# TeensyRF.net
KiCad netlist of a schematic drawn in EAGLE
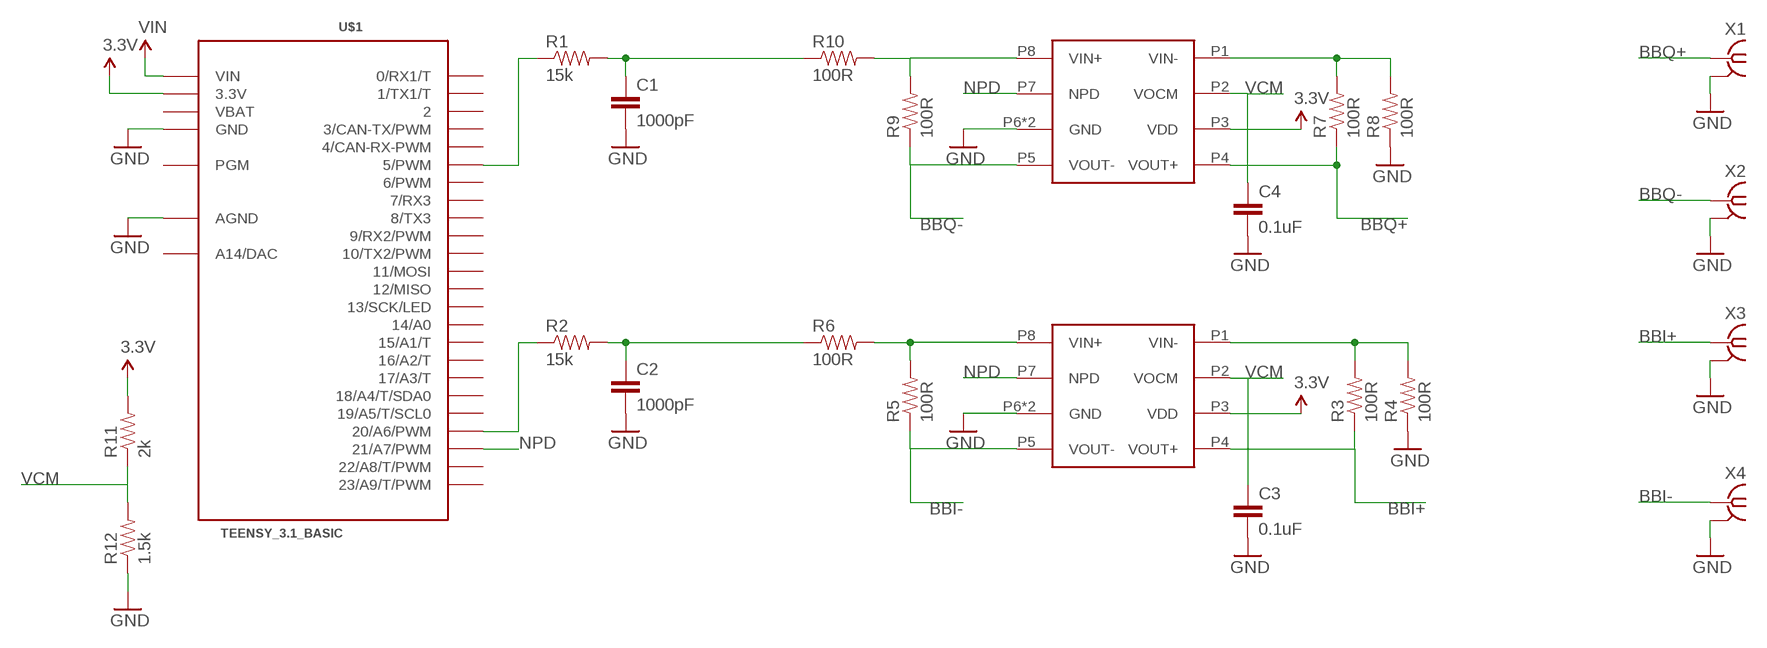
[diagram p0: schematic, sheet 1]

(export (version "E")
  (design (tool "Eeschema 10.0.6"))
  (components
    (comp (ref "C1")
      (value "1000pF")
      (footprint "eagle-import:0805")
      (libsource (lib "eagle-import") (part "CAP0805"))
    )
    (comp (ref "C2")
      (value "1000pF")
      (footprint "eagle-import:0805")
      (libsource (lib "eagle-import") (part "CAP0805"))
    )
    (comp (ref "C3")
      (value "0.1uF")
      (footprint "eagle-import:0805")
      (libsource (lib "eagle-import") (part "CAP0805"))
    )
    (comp (ref "C4")
      (value "0.1uF")
      (footprint "eagle-import:0805")
      (libsource (lib "eagle-import") (part "CAP0805"))
    )
    (comp (ref "R1")
      (value "15k")
      (footprint "eagle-import:0805")
      (libsource (lib "eagle-import") (part "RESISTOR0805-RES"))
    )
    (comp (ref "R2")
      (value "15k")
      (footprint "eagle-import:0805")
      (libsource (lib "eagle-import") (part "RESISTOR0805-RES"))
    )
    (comp (ref "R3")
      (value "100R")
      (footprint "eagle-import:0805")
      (libsource (lib "eagle-import") (part "RESISTOR0805-RES"))
    )
    (comp (ref "R4")
      (value "100R")
      (footprint "eagle-import:0805")
      (libsource (lib "eagle-import") (part "RESISTOR0805-RES"))
    )
    (comp (ref "R5")
      (value "100R")
      (footprint "eagle-import:0805")
      (libsource (lib "eagle-import") (part "RESISTOR0805-RES"))
    )
    (comp (ref "R6")
      (value "100R")
      (footprint "eagle-import:0805")
      (libsource (lib "eagle-import") (part "RESISTOR0805-RES"))
    )
    (comp (ref "R7")
      (value "100R")
      (footprint "eagle-import:0805")
      (libsource (lib "eagle-import") (part "RESISTOR0805-RES"))
    )
    (comp (ref "R8")
      (value "100R")
      (footprint "eagle-import:0805")
      (libsource (lib "eagle-import") (part "RESISTOR0805-RES"))
    )
    (comp (ref "R9")
      (value "100R")
      (footprint "eagle-import:0805")
      (libsource (lib "eagle-import") (part "RESISTOR0805-RES"))
    )
    (comp (ref "R10")
      (value "100R")
      (footprint "eagle-import:0805")
      (libsource (lib "eagle-import") (part "RESISTOR0805-RES"))
    )
    (comp (ref "R11")
      (value "2k")
      (footprint "eagle-import:0805")
      (libsource (lib "eagle-import") (part "RESISTOR0805-RES"))
    )
    (comp (ref "R12")
      (value "1.5k")
      (footprint "eagle-import:0805")
      (libsource (lib "eagle-import") (part "RESISTOR0805-RES"))
    )
    (comp (ref "U$1")
      (value "TEENSY_3.1_BASIC")
      (footprint "eagle-import:TEENSY_3.1_BASIC")
      (libsource (lib "eagle-import") (part "TEENSY_3.1_BASIC"))
    )
    (comp (ref "U$2")
      (value "THS4120")
      (footprint "eagle-import:POWERPAD-MSOP-8")
      (libsource (lib "eagle-import") (part "THS4120"))
    )
    (comp (ref "U$3")
      (value "THS4120")
      (footprint "eagle-import:POWERPAD-MSOP-8")
      (libsource (lib "eagle-import") (part "THS4120"))
    )
    (comp (ref "X1")
      (value "SMA-142-0701-801/806")
      (footprint "eagle-import:J502-ND-142-0701-801_806")
      (fields (field (name "MF") "JOHNSON COMPONENTS") (field (name "MPN") "142-0701-801"))
      (libsource (lib "eagle-import") (part "SMA-142-0701-801/806"))
    )
    (comp (ref "X2")
      (value "SMA-142-0701-801/806")
      (footprint "eagle-import:J502-ND-142-0701-801_806")
      (fields (field (name "MF") "JOHNSON COMPONENTS") (field (name "MPN") "142-0701-801"))
      (libsource (lib "eagle-import") (part "SMA-142-0701-801/806"))
    )
    (comp (ref "X3")
      (value "SMA-142-0701-801/806")
      (footprint "eagle-import:J502-ND-142-0701-801_806")
      (fields (field (name "MF") "JOHNSON COMPONENTS") (field (name "MPN") "142-0701-801"))
      (libsource (lib "eagle-import") (part "SMA-142-0701-801/806"))
    )
    (comp (ref "X4")
      (value "SMA-142-0701-801/806")
      (footprint "eagle-import:J502-ND-142-0701-801_806")
      (fields (field (name "MF") "JOHNSON COMPONENTS") (field (name "MPN") "142-0701-801"))
      (libsource (lib "eagle-import") (part "SMA-142-0701-801/806"))
    )
  )
  (nets
    (net (code "1") (name "/BBI+") (class "Default")
      (node (ref "R3") (pin "1") (pinfunction "1_1") (pintype "passive"))
      (node (ref "U$3") (pin "P4") (pinfunction "VOUT+_P4") (pintype "bidirectional"))
      (node (ref "X3") (pin "1") (pinfunction "1_1") (pintype "passive"))
    )
    (net (code "2") (name "/BBI-") (class "Default")
      (node (ref "R5") (pin "1") (pinfunction "1_1") (pintype "passive"))
      (node (ref "U$3") (pin "P5") (pinfunction "VOUT-_P5") (pintype "bidirectional"))
      (node (ref "X4") (pin "1") (pinfunction "1_1") (pintype "passive"))
    )
    (net (code "3") (name "/BBQ+") (class "Default")
      (node (ref "R7") (pin "1") (pinfunction "1_1") (pintype "passive"))
      (node (ref "U$2") (pin "P4") (pinfunction "VOUT+_P4") (pintype "bidirectional"))
      (node (ref "X1") (pin "1") (pinfunction "1_1") (pintype "passive"))
    )
    (net (code "4") (name "/BBQ-") (class "Default")
      (node (ref "R9") (pin "1") (pinfunction "1_1") (pintype "passive"))
      (node (ref "U$2") (pin "P5") (pinfunction "VOUT-_P5") (pintype "bidirectional"))
      (node (ref "X2") (pin "1") (pinfunction "1_1") (pintype "passive"))
    )
    (net (code "5") (name "/NPD") (class "Default")
      (node (ref "U$1") (pin "21/A7") (pinfunction "21/A7/PWM_21/A7") (pintype "bidirectional"))
      (node (ref "U$2") (pin "P7") (pinfunction "NPD_P7") (pintype "bidirectional"))
      (node (ref "U$3") (pin "P7") (pinfunction "NPD_P7") (pintype "bidirectional"))
    )
    (net (code "6") (name "/VBAT") (class "Default")
      (node (ref "U$1") (pin "VBAT") (pinfunction "VBAT_VBAT") (pintype "power_in"))
    )
    (net (code "7") (name "/VCM") (class "Default")
      (node (ref "C3") (pin "1") (pinfunction "1_1") (pintype "passive"))
      (node (ref "C4") (pin "1") (pinfunction "1_1") (pintype "passive"))
      (node (ref "R11") (pin "1") (pinfunction "1_1") (pintype "passive"))
      (node (ref "R12") (pin "2") (pinfunction "2_2") (pintype "passive"))
      (node (ref "U$2") (pin "P2") (pinfunction "VOCM_P2") (pintype "bidirectional"))
      (node (ref "U$3") (pin "P2") (pinfunction "VOCM_P2") (pintype "bidirectional"))
    )
    (net (code "8") (name "3.3V") (class "Default")
      (node (ref "R11") (pin "2") (pinfunction "2_2") (pintype "passive"))
      (node (ref "U$1") (pin "3.3V") (pinfunction "3.3V_3.3V") (pintype "power_in"))
      (node (ref "U$1") (pin "3.3V1") (pinfunction "3.3V_3.3V1") (pintype "power_in"))
      (node (ref "U$2") (pin "P3") (pinfunction "VDD_P3") (pintype "bidirectional"))
      (node (ref "U$3") (pin "P3") (pinfunction "VDD_P3") (pintype "bidirectional"))
    )
    (net (code "9") (name "GND") (class "Default")
      (node (ref "C1") (pin "2") (pinfunction "2_2") (pintype "passive"))
      (node (ref "C2") (pin "2") (pinfunction "2_2") (pintype "passive"))
      (node (ref "C3") (pin "2") (pinfunction "2_2") (pintype "passive"))
      (node (ref "C4") (pin "2") (pinfunction "2_2") (pintype "passive"))
      (node (ref "R12") (pin "1") (pinfunction "1_1") (pintype "passive"))
      (node (ref "R4") (pin "1") (pinfunction "1_1") (pintype "passive"))
      (node (ref "R8") (pin "1") (pinfunction "1_1") (pintype "passive"))
      (node (ref "U$1") (pin "AGND") (pinfunction "AGND_AGND") (pintype "power_in"))
      (node (ref "U$1") (pin "GND") (pinfunction "GND_GND") (pintype "power_in"))
      (node (ref "U$1") (pin "GND1") (pinfunction "GND_GND1") (pintype "power_in"))
      (node (ref "U$2") (pin "P6") (pinfunction "GND_P6") (pintype "bidirectional"))
      (node (ref "U$2") (pin "PAD") (pinfunction "GND_PAD") (pintype "bidirectional"))
      (node (ref "U$3") (pin "P6") (pinfunction "GND_P6") (pintype "bidirectional"))
      (node (ref "U$3") (pin "PAD") (pinfunction "GND_PAD") (pintype "bidirectional"))
      (node (ref "X1") (pin "G@1") (pinfunction "2_G@1") (pintype "passive"))
      (node (ref "X1") (pin "G@2") (pinfunction "2_G@2") (pintype "passive"))
      (node (ref "X1") (pin "G@3") (pinfunction "2_G@3") (pintype "passive"))
      (node (ref "X1") (pin "G@4") (pinfunction "2_G@4") (pintype "passive"))
      (node (ref "X2") (pin "G@1") (pinfunction "2_G@1") (pintype "passive"))
      (node (ref "X2") (pin "G@2") (pinfunction "2_G@2") (pintype "passive"))
      (node (ref "X2") (pin "G@3") (pinfunction "2_G@3") (pintype "passive"))
      (node (ref "X2") (pin "G@4") (pinfunction "2_G@4") (pintype "passive"))
      (node (ref "X3") (pin "G@1") (pinfunction "2_G@1") (pintype "passive"))
      (node (ref "X3") (pin "G@2") (pinfunction "2_G@2") (pintype "passive"))
      (node (ref "X3") (pin "G@3") (pinfunction "2_G@3") (pintype "passive"))
      (node (ref "X3") (pin "G@4") (pinfunction "2_G@4") (pintype "passive"))
      (node (ref "X4") (pin "G@1") (pinfunction "2_G@1") (pintype "passive"))
      (node (ref "X4") (pin "G@2") (pinfunction "2_G@2") (pintype "passive"))
      (node (ref "X4") (pin "G@3") (pinfunction "2_G@3") (pintype "passive"))
      (node (ref "X4") (pin "G@4") (pinfunction "2_G@4") (pintype "passive"))
    )
    (net (code "10") (name "Net-(C1-Pad1)") (class "Default")
      (node (ref "C1") (pin "1") (pinfunction "1_1") (pintype "passive"))
      (node (ref "R1") (pin "2") (pinfunction "2_2") (pintype "passive"))
      (node (ref "R10") (pin "1") (pinfunction "1_1") (pintype "passive"))
    )
    (net (code "11") (name "Net-(C2-Pad1)") (class "Default")
      (node (ref "C2") (pin "1") (pinfunction "1_1") (pintype "passive"))
      (node (ref "R2") (pin "2") (pinfunction "2_2") (pintype "passive"))
      (node (ref "R6") (pin "1") (pinfunction "1_1") (pintype "passive"))
    )
    (net (code "12") (name "Net-(U$1-5{slash}PWM)") (class "Default")
      (node (ref "R1") (pin "1") (pinfunction "1_1") (pintype "passive"))
      (node (ref "U$1") (pin "5") (pinfunction "5/PWM_5") (pintype "bidirectional"))
    )
    (net (code "13") (name "Net-(U$1-20{slash}A6{slash}PWM)") (class "Default")
      (node (ref "R2") (pin "1") (pinfunction "1_1") (pintype "passive"))
      (node (ref "U$1") (pin "20/A6") (pinfunction "20/A6/PWM_20/A6") (pintype "bidirectional"))
    )
    (net (code "14") (name "Net-(U$2-VIN+)") (class "Default")
      (node (ref "R10") (pin "2") (pinfunction "2_2") (pintype "passive"))
      (node (ref "R9") (pin "2") (pinfunction "2_2") (pintype "passive"))
      (node (ref "U$2") (pin "P8") (pinfunction "VIN+_P8") (pintype "bidirectional"))
    )
    (net (code "15") (name "Net-(U$2-VIN-)") (class "Default")
      (node (ref "R7") (pin "2") (pinfunction "2_2") (pintype "passive"))
      (node (ref "R8") (pin "2") (pinfunction "2_2") (pintype "passive"))
      (node (ref "U$2") (pin "P1") (pinfunction "VIN-_P1") (pintype "bidirectional"))
    )
    (net (code "16") (name "Net-(U$3-VIN+)") (class "Default")
      (node (ref "R5") (pin "2") (pinfunction "2_2") (pintype "passive"))
      (node (ref "R6") (pin "2") (pinfunction "2_2") (pintype "passive"))
      (node (ref "U$3") (pin "P8") (pinfunction "VIN+_P8") (pintype "bidirectional"))
    )
    (net (code "17") (name "Net-(U$3-VIN-)") (class "Default")
      (node (ref "R3") (pin "2") (pinfunction "2_2") (pintype "passive"))
      (node (ref "R4") (pin "2") (pinfunction "2_2") (pintype "passive"))
      (node (ref "U$3") (pin "P1") (pinfunction "VIN-_P1") (pintype "bidirectional"))
    )
    (net (code "18") (name "VIN") (class "Default")
      (node (ref "U$1") (pin "VIN") (pinfunction "VIN_VIN") (pintype "power_in"))
    )
    (net (code "19") (name "unconnected-(U$1-0{slash}RX1{slash}T-Pad0)") (class "Default")
      (node (ref "U$1") (pin "0") (pinfunction "0/RX1/T_0") (pintype "bidirectional"))
    )
    (net (code "20") (name "unconnected-(U$1-1{slash}TX1{slash}T-Pad1)") (class "Default")
      (node (ref "U$1") (pin "1") (pinfunction "1/TX1/T_1") (pintype "bidirectional"))
    )
    (net (code "21") (name "unconnected-(U$1-3{slash}CAN-TX{slash}PWM-Pad3)") (class "Default")
      (node (ref "U$1") (pin "3") (pinfunction "3/CAN-TX/PWM_3") (pintype "bidirectional"))
    )
    (net (code "22") (name "unconnected-(U$1-4{slash}CAN-RX-PWM-Pad4)") (class "Default")
      (node (ref "U$1") (pin "4") (pinfunction "4/CAN-RX-PWM_4") (pintype "bidirectional"))
    )
    (net (code "23") (name "unconnected-(U$1-6{slash}PWM-Pad6)") (class "Default")
      (node (ref "U$1") (pin "6") (pinfunction "6/PWM_6") (pintype "bidirectional"))
    )
    (net (code "24") (name "unconnected-(U$1-7{slash}RX3-Pad7)") (class "Default")
      (node (ref "U$1") (pin "7") (pinfunction "7/RX3_7") (pintype "bidirectional"))
    )
    (net (code "25") (name "unconnected-(U$1-8{slash}TX3-Pad8)") (class "Default")
      (node (ref "U$1") (pin "8") (pinfunction "8/TX3_8") (pintype "bidirectional"))
    )
    (net (code "26") (name "unconnected-(U$1-9{slash}RX2{slash}PWM-Pad9)") (class "Default")
      (node (ref "U$1") (pin "9") (pinfunction "9/RX2/PWM_9") (pintype "bidirectional"))
    )
    (net (code "27") (name "unconnected-(U$1-10{slash}TX2{slash}PWM-Pad10)") (class "Default")
      (node (ref "U$1") (pin "10") (pinfunction "10/TX2/PWM_10") (pintype "bidirectional"))
    )
    (net (code "28") (name "unconnected-(U$1-11{slash}MOSI-Pad11)") (class "Default")
      (node (ref "U$1") (pin "11") (pinfunction "11/MOSI_11") (pintype "bidirectional"))
    )
    (net (code "29") (name "unconnected-(U$1-12{slash}MISO-Pad12)") (class "Default")
      (node (ref "U$1") (pin "12") (pinfunction "12/MISO_12") (pintype "bidirectional"))
    )
    (net (code "30") (name "unconnected-(U$1-13{slash}SCK{slash}LED-Pad13)") (class "Default")
      (node (ref "U$1") (pin "13") (pinfunction "13/SCK/LED_13") (pintype "bidirectional"))
    )
    (net (code "31") (name "unconnected-(U$1-15{slash}A1{slash}T-Pad15{slash}A1)") (class "Default")
      (node (ref "U$1") (pin "15/A1") (pinfunction "15/A1/T_15/A1") (pintype "bidirectional"))
    )
    (net (code "32") (name "unconnected-(U$1-16{slash}A2{slash}T-Pad16{slash}A2)") (class "Default")
      (node (ref "U$1") (pin "16/A2") (pinfunction "16/A2/T_16/A2") (pintype "bidirectional"))
    )
    (net (code "33") (name "unconnected-(U$1-17{slash}A3{slash}T-Pad17{slash}A3)") (class "Default")
      (node (ref "U$1") (pin "17/A3") (pinfunction "17/A3/T_17/A3") (pintype "bidirectional"))
    )
    (net (code "34") (name "unconnected-(U$1-18{slash}A4{slash}T{slash}SDA0-Pad18{slash}A4)") (class "Default")
      (node (ref "U$1") (pin "18/A4") (pinfunction "18/A4/T/SDA0_18/A4") (pintype "bidirectional"))
    )
    (net (code "35") (name "unconnected-(U$1-19{slash}A5{slash}T{slash}SCL0-Pad19{slash}A5)") (class "Default")
      (node (ref "U$1") (pin "19/A5") (pinfunction "19/A5/T/SCL0_19/A5") (pintype "bidirectional"))
    )
    (net (code "36") (name "unconnected-(U$1-22{slash}A8{slash}T{slash}PWM-Pad22{slash}A8)") (class "Default")
      (node (ref "U$1") (pin "22/A8") (pinfunction "22/A8/T/PWM_22/A8") (pintype "bidirectional"))
    )
    (net (code "37") (name "unconnected-(U$1-23{slash}A9{slash}T{slash}PWM-Pad23{slash}A9)") (class "Default")
      (node (ref "U$1") (pin "23/A9") (pinfunction "23/A9/T/PWM_23/A9") (pintype "bidirectional"))
    )
    (net (code "38") (name "unconnected-(U$1-A14{slash}DAC-PadA14)") (class "Default")
      (node (ref "U$1") (pin "A14") (pinfunction "A14/DAC_A14") (pintype "bidirectional"))
    )
    (net (code "39") (name "unconnected-(U$1-Pad2)") (class "Default")
      (node (ref "U$1") (pin "2") (pinfunction "2_2") (pintype "bidirectional"))
    )
    (net (code "40") (name "unconnected-(U$1-Pad14{slash}A0)") (class "Default")
      (node (ref "U$1") (pin "14/A0") (pinfunction "14/A0_14/A0") (pintype "bidirectional"))
    )
    (net (code "41") (name "unconnected-(U$1-PadPGM)") (class "Default")
      (node (ref "U$1") (pin "PGM") (pinfunction "PGM_PGM") (pintype "bidirectional"))
    )
  )
)
